# charger_v4.net
KiCad netlist of a schematic drawn in EAGLE
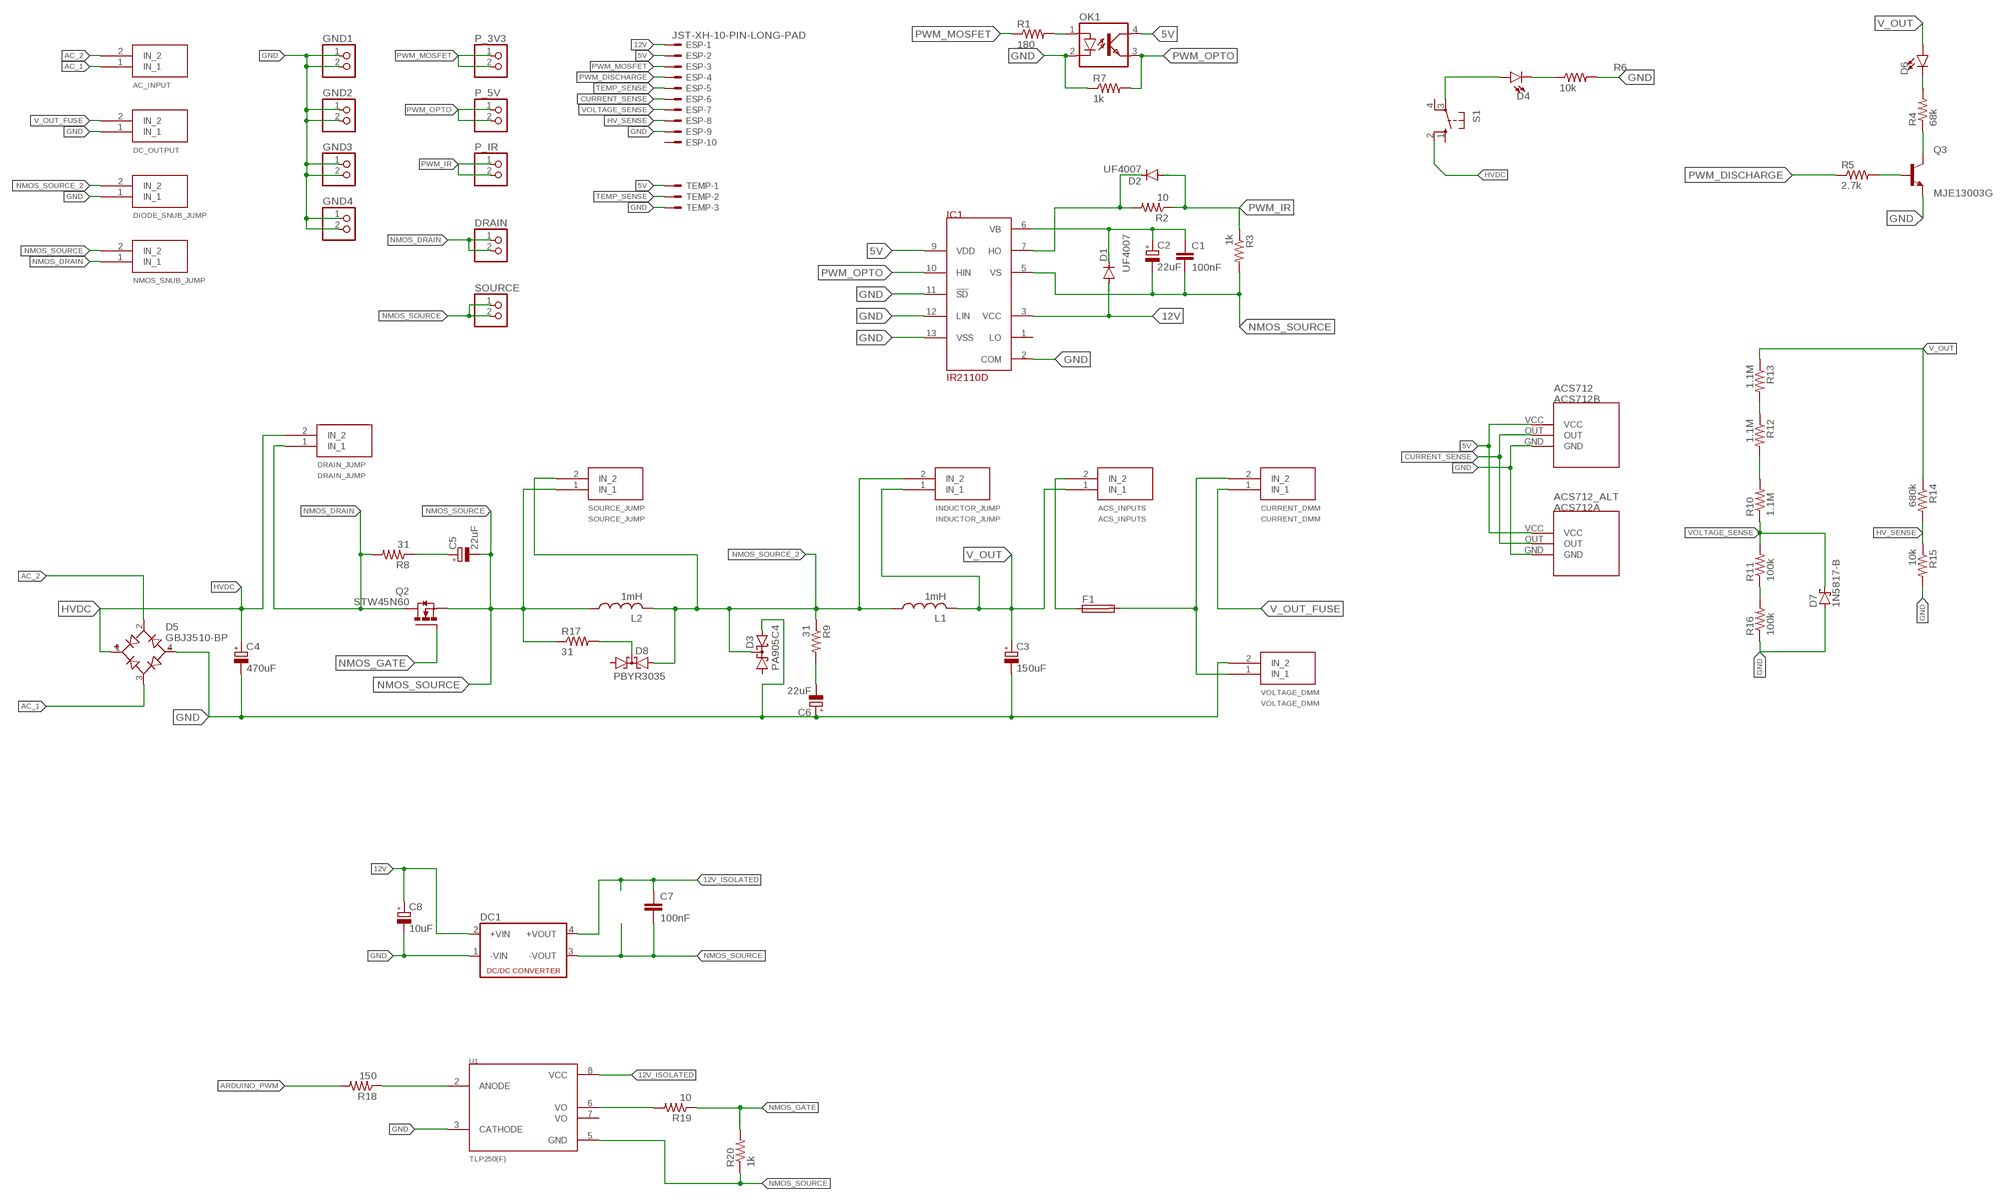
[diagram p0: schematic, sheet 1]

(export (version "E")
  (design (tool "Eeschema 10.0.6"))
  (components
    (comp (ref "ACS712")
      (value "ACS712B")
      (footprint "eagle-import:ACS712-2")
      (libsource (lib "eagle-import") (part "ACS712B"))
    )
    (comp (ref "ACS712_ALT")
      (value "ACS712A")
      (footprint "eagle-import:ACS712-1")
      (libsource (lib "eagle-import") (part "ACS712A"))
    )
    (comp (ref "ACS_INPUTS")
      (value "ACS_INPUTS")
      (footprint "eagle-import:TERMINAL_2P")
      (libsource (lib "eagle-import") (part "TERMINAL_2P"))
    )
    (comp (ref "AC_INPUT")
      (value "AC_INPUT")
      (footprint "eagle-import:TERMINAL_2P")
      (libsource (lib "eagle-import") (part "TERMINAL_2P"))
    )
    (comp (ref "C1")
      (value "100nF")
      (footprint "eagle-import:C025-025X050")
      (libsource (lib "eagle-import") (part "C-EU025-025X050"))
    )
    (comp (ref "C2")
      (value "22uF")
      (footprint "eagle-import:E2,5-6E")
      (libsource (lib "eagle-import") (part "CPOL-EUE2,5-6E"))
    )
    (comp (ref "C3")
      (value "150uF")
      (footprint "eagle-import:E7,5-18")
      (libsource (lib "eagle-import") (part "CPOL-EUE7.5-18"))
    )
    (comp (ref "C4")
      (value "470uF")
      (footprint "eagle-import:EB35D")
      (libsource (lib "eagle-import") (part "CPOL-EUE10-35"))
    )
    (comp (ref "C5")
      (value "22uF")
      (footprint "eagle-import:ETR4")
      (libsource (lib "eagle-import") (part "CPOL-EUETR4"))
    )
    (comp (ref "C6")
      (value "22uF")
      (footprint "eagle-import:ETR4")
      (libsource (lib "eagle-import") (part "CPOL-EUETR4"))
    )
    (comp (ref "C7")
      (value "100nF")
      (footprint "eagle-import:C025-025X050")
      (libsource (lib "eagle-import") (part "C-EU025-025X050"))
    )
    (comp (ref "C8")
      (value "10uF")
      (footprint "eagle-import:E2,5-6E")
      (libsource (lib "eagle-import") (part "CPOL-EUE2,5-6E"))
    )
    (comp (ref "CURRENT_DMM")
      (value "CURRENT_DMM")
      (footprint "eagle-import:TERMINAL_2P")
      (libsource (lib "eagle-import") (part "TERMINAL_2P"))
    )
    (comp (ref "D1")
      (value "UF4007")
      (footprint "eagle-import:DO34-7")
      (libsource (lib "eagle-import") (part "BAS15"))
    )
    (comp (ref "D2")
      (value "UF4007")
      (footprint "eagle-import:DO34-7")
      (libsource (lib "eagle-import") (part "BAS15"))
    )
    (comp (ref "D3")
      (value "PA905C4")
      (footprint "eagle-import:SOT93S")
      (libsource (lib "eagle-import") (part "PBYR3035"))
    )
    (comp (ref "D4")
      (value "LED5MM")
      (footprint "eagle-import:LED_5MM")
      (libsource (lib "eagle-import") (part "LED5MM"))
    )
    (comp (ref "D5")
      (value "GBJ3510-BP")
      (footprint "eagle-import:DIOB_GBJ3510-BP")
      (fields (field (name "MF") "Micro Commercial"))
      (libsource (lib "eagle-import") (part "GBJ3510-BP"))
    )
    (comp (ref "D6")
      (value "LED5MM")
      (footprint "eagle-import:LED_5MM")
      (libsource (lib "eagle-import") (part "LED5MM"))
    )
    (comp (ref "D7")
      (value "1N5817-B")
      (footprint "eagle-import:DO41-7.6")
      (libsource (lib "eagle-import") (part "1N5817-B"))
    )
    (comp (ref "D8")
      (value "PBYR3035")
      (footprint "eagle-import:SOT93S")
      (libsource (lib "eagle-import") (part "PBYR3035"))
    )
    (comp (ref "DC1")
      (value "NME")
      (footprint "eagle-import:NME")
      (fields (field (name "MF") "C & D TECHNOLOGIES, INC") (field (name "MPN") "NME1205D"))
      (libsource (lib "eagle-import") (part "NME"))
    )
    (comp (ref "DC_OUTPUT")
      (value "DC_OUTPUT")
      (footprint "eagle-import:TERMINAL_2P")
      (libsource (lib "eagle-import") (part "TERMINAL_2P"))
    )
    (comp (ref "DIODE_SNUB_JUMP")
      (value "DIODE_SNUB_JUMP")
      (footprint "eagle-import:TERMINAL_2P")
      (libsource (lib "eagle-import") (part "TERMINAL_2P"))
    )
    (comp (ref "DRAIN")
      (value "PINHD-1X2")
      (footprint "eagle-import:1X02")
      (libsource (lib "eagle-import") (part "PINHD-1X2"))
    )
    (comp (ref "DRAIN_JUMP")
      (value "DRAIN_JUMP")
      (footprint "eagle-import:TERMINAL_2P")
      (libsource (lib "eagle-import") (part "TERMINAL_2P"))
    )
    (comp (ref "ESP")
      (value "JST-XH-10-PIN-LONG-PAD")
      (footprint "eagle-import:JST-XH-10-PACKAGE-LONG-PAD")
      (libsource (lib "eagle-import") (part "JST-XH-10-PIN-LONG-PAD"))
    )
    (comp (ref "F1")
      (value "FUSEHOLDER")
      (footprint "eagle-import:FUSEHOLDER")
      (fields (field (name "MPN") "0031.7701.11"))
      (libsource (lib "eagle-import") (part "FUSEHOLDER"))
    )
    (comp (ref "GND1")
      (value "PINHD-1X2")
      (footprint "eagle-import:1X02")
      (libsource (lib "eagle-import") (part "PINHD-1X2"))
    )
    (comp (ref "GND2")
      (value "PINHD-1X2")
      (footprint "eagle-import:1X02")
      (libsource (lib "eagle-import") (part "PINHD-1X2"))
    )
    (comp (ref "GND3")
      (value "PINHD-1X2")
      (footprint "eagle-import:1X02")
      (libsource (lib "eagle-import") (part "PINHD-1X2"))
    )
    (comp (ref "GND4")
      (value "PINHD-1X2")
      (footprint "eagle-import:1X02")
      (libsource (lib "eagle-import") (part "PINHD-1X2"))
    )
    (comp (ref "IC1")
      (value "IR2110D")
      (footprint "eagle-import:DIL14")
      (libsource (lib "eagle-import") (part "IR2110D"))
    )
    (comp (ref "INDUCTOR_JUMP")
      (value "INDUCTOR_JUMP")
      (footprint "eagle-import:TERMINAL_2P")
      (libsource (lib "eagle-import") (part "TERMINAL_2P"))
    )
    (comp (ref "L1")
      (value "1mH")
      (footprint "eagle-import:TJ7-U1")
      (libsource (lib "eagle-import") (part "L-USTJ7-U1"))
    )
    (comp (ref "L2")
      (value "1mH")
      (footprint "eagle-import:TJ7-U1")
      (libsource (lib "eagle-import") (part "L-USTJ7-U1"))
    )
    (comp (ref "NMOS_SNUB_JUMP")
      (value "NMOS_SNUB_JUMP")
      (footprint "eagle-import:TERMINAL_2P")
      (libsource (lib "eagle-import") (part "TERMINAL_2P"))
    )
    (comp (ref "OK1")
      (value "SFH618A-5")
      (footprint "eagle-import:DIP4")
      (fields (field (name "MF") "VISHAY/TELEFUNKEN"))
      (libsource (lib "eagle-import") (part "SFH618?A-5"))
    )
    (comp (ref "P_3V3")
      (value "PINHD-1X2")
      (footprint "eagle-import:1X02")
      (libsource (lib "eagle-import") (part "PINHD-1X2"))
    )
    (comp (ref "P_5V")
      (value "PINHD-1X2")
      (footprint "eagle-import:1X02")
      (libsource (lib "eagle-import") (part "PINHD-1X2"))
    )
    (comp (ref "P_IR")
      (value "PINHD-1X2")
      (footprint "eagle-import:1X02")
      (libsource (lib "eagle-import") (part "PINHD-1X2"))
    )
    (comp (ref "Q2")
      (value "STW45N60")
      (footprint "eagle-import:TO247AC")
      (fields (field (name "MF") "Vishay Siliconix") (field (name "MP") "IRFP240"))
      (libsource (lib "eagle-import") (part "IRFP240"))
    )
    (comp (ref "Q3")
      (value "MJE13003G")
      (footprint "eagle-import:TO229P780X300X1364-3")
      (fields (field (name "MF") "ON Semiconductor"))
      (libsource (lib "eagle-import") (part "MJE13003G"))
    )
    (comp (ref "R1")
      (value "180")
      (footprint "eagle-import:0204_7")
      (libsource (lib "eagle-import") (part "R-US_0204/7"))
    )
    (comp (ref "R2")
      (value "10")
      (footprint "eagle-import:0204_7")
      (libsource (lib "eagle-import") (part "R-US_0204/7"))
    )
    (comp (ref "R3")
      (value "1k")
      (footprint "eagle-import:0204_7")
      (libsource (lib "eagle-import") (part "R-US_0204/7"))
    )
    (comp (ref "R4")
      (value "68k")
      (footprint "eagle-import:0411_15")
      (libsource (lib "eagle-import") (part "R-US_0411/15"))
    )
    (comp (ref "R5")
      (value "2.7k")
      (footprint "eagle-import:0204_7")
      (libsource (lib "eagle-import") (part "R-US_0204/7"))
    )
    (comp (ref "R6")
      (value "10k")
      (footprint "eagle-import:0204_7")
      (libsource (lib "eagle-import") (part "R-US_0204/7"))
    )
    (comp (ref "R7")
      (value "1k")
      (footprint "eagle-import:0204_7")
      (libsource (lib "eagle-import") (part "R-US_0204/7"))
    )
    (comp (ref "R8")
      (value "31")
      (footprint "eagle-import:0411_15")
      (libsource (lib "eagle-import") (part "R-US_0411/15"))
    )
    (comp (ref "R9")
      (value "31")
      (footprint "eagle-import:0411_15")
      (libsource (lib "eagle-import") (part "R-US_0411/15"))
    )
    (comp (ref "R10")
      (value "1.1M")
      (footprint "eagle-import:R0805")
      (libsource (lib "eagle-import") (part "R-US_R0805"))
    )
    (comp (ref "R11")
      (value "100k")
      (footprint "eagle-import:R0805")
      (libsource (lib "eagle-import") (part "R-US_R0805"))
    )
    (comp (ref "R12")
      (value "1.1M")
      (footprint "eagle-import:R0805")
      (libsource (lib "eagle-import") (part "R-US_R0805"))
    )
    (comp (ref "R13")
      (value "1.1M")
      (footprint "eagle-import:R0805")
      (libsource (lib "eagle-import") (part "R-US_R0805"))
    )
    (comp (ref "R14")
      (value "680k")
      (footprint "eagle-import:0207_10")
      (libsource (lib "eagle-import") (part "R-US_0207/10"))
    )
    (comp (ref "R15")
      (value "10k")
      (footprint "eagle-import:0207_10")
      (libsource (lib "eagle-import") (part "R-US_0207/10"))
    )
    (comp (ref "R16")
      (value "100k")
      (footprint "eagle-import:R0805")
      (libsource (lib "eagle-import") (part "R-US_R0805"))
    )
    (comp (ref "R17")
      (value "31")
      (footprint "eagle-import:0411_15")
      (libsource (lib "eagle-import") (part "R-US_0411/15"))
    )
    (comp (ref "R18")
      (value "150")
      (footprint "eagle-import:0204_7")
      (libsource (lib "eagle-import") (part "R-US_0204/7"))
    )
    (comp (ref "R19")
      (value "10")
      (footprint "eagle-import:0204_7")
      (libsource (lib "eagle-import") (part "R-US_0204/7"))
    )
    (comp (ref "R20")
      (value "1k")
      (footprint "eagle-import:0204_7")
      (libsource (lib "eagle-import") (part "R-US_0204/7"))
    )
    (comp (ref "S1")
      (value "10-XX")
      (footprint "eagle-import:B3F-10XX")
      (fields (field (name "MPN") "B3F-1000"))
      (libsource (lib "eagle-import") (part "10-XX"))
    )
    (comp (ref "SOURCE")
      (value "PINHD-1X2")
      (footprint "eagle-import:1X02")
      (libsource (lib "eagle-import") (part "PINHD-1X2"))
    )
    (comp (ref "SOURCE_JUMP")
      (value "SOURCE_JUMP")
      (footprint "eagle-import:TERMINAL_2P")
      (libsource (lib "eagle-import") (part "TERMINAL_2P"))
    )
    (comp (ref "TEMP")
      (value "JST-XH-03-PIN-LONG-PAD")
      (footprint "eagle-import:JST-XH-03-PACKAGE-LONG-PAD")
      (libsource (lib "eagle-import") (part "JST-XH-03-PIN-LONG-PAD"))
    )
    (comp (ref "U1")
      (value "TLP250(F)")
      (footprint "eagle-import:DIP1016W50P254L966H380Q8P")
      (fields (field (name "MF") "Toshiba"))
      (libsource (lib "eagle-import") (part "TLP250(F)"))
    )
    (comp (ref "VOLTAGE_DMM")
      (value "VOLTAGE_DMM")
      (footprint "eagle-import:TERMINAL_2P")
      (libsource (lib "eagle-import") (part "TERMINAL_2P"))
    )
  )
  (nets
    (net (code "1") (name "5V") (class "Default")
      (node (ref "ACS712") (pin "VCC") (pinfunction "VCC_VCC") (pintype "bidirectional"))
      (node (ref "ACS712_ALT") (pin "VCC") (pinfunction "VCC_VCC") (pintype "bidirectional"))
      (node (ref "ESP") (pin "2") (pinfunction "S_2") (pintype "passive"))
      (node (ref "IC1") (pin "9") (pinfunction "VDD_9") (pintype "power_in"))
      (node (ref "OK1") (pin "4") (pinfunction "COL_4") (pintype "passive"))
      (node (ref "TEMP") (pin "1") (pinfunction "S_1") (pintype "passive"))
    )
    (net (code "2") (name "12V") (class "Default")
      (node (ref "C8") (pin "+") (pinfunction "+_+") (pintype "passive"))
      (node (ref "D1") (pin "A") (pinfunction "A_A") (pintype "passive"))
      (node (ref "DC1") (pin "2") (pinfunction "+VIN_2") (pintype "passive"))
      (node (ref "ESP") (pin "1") (pinfunction "S_1") (pintype "passive"))
      (node (ref "IC1") (pin "3") (pinfunction "VCC_3") (pintype "power_in"))
    )
    (net (code "3") (name "12V_ISOLATED") (class "Default")
      (node (ref "C7") (pin "1") (pinfunction "1_1") (pintype "passive"))
      (node (ref "DC1") (pin "4") (pinfunction "+VOUT_4") (pintype "passive"))
      (node (ref "U1") (pin "8") (pinfunction "VCC_8") (pintype "power_in"))
    )
    (net (code "4") (name "AC_1") (class "Default")
      (node (ref "AC_INPUT") (pin "1") (pinfunction "IN_1_1") (pintype "bidirectional"))
      (node (ref "D5") (pin "3") (pinfunction "AC2_3") (pintype "passive"))
    )
    (net (code "5") (name "AC_2") (class "Default")
      (node (ref "AC_INPUT") (pin "2") (pinfunction "IN_2_2") (pintype "bidirectional"))
      (node (ref "D5") (pin "2") (pinfunction "AC1_2") (pintype "passive"))
    )
    (net (code "6") (name "ARDUINO_PWM") (class "Default")
      (node (ref "R18") (pin "2") (pinfunction "2_2") (pintype "passive"))
    )
    (net (code "7") (name "CURRENT_SENSE") (class "Default")
      (node (ref "ACS712") (pin "OUT") (pinfunction "OUT_OUT") (pintype "bidirectional"))
      (node (ref "ACS712_ALT") (pin "OUT") (pinfunction "OUT_OUT") (pintype "bidirectional"))
      (node (ref "ESP") (pin "6") (pinfunction "S_6") (pintype "passive"))
    )
    (net (code "8") (name "GND") (class "Default")
      (node (ref "ACS712") (pin "GND") (pinfunction "GND_GND") (pintype "bidirectional"))
      (node (ref "ACS712_ALT") (pin "GND") (pinfunction "GND_GND") (pintype "bidirectional"))
      (node (ref "C3") (pin "-") (pinfunction "-_-") (pintype "passive"))
      (node (ref "C4") (pin "-") (pinfunction "-_-") (pintype "passive"))
      (node (ref "C6") (pin "+") (pinfunction "+_+") (pintype "passive"))
      (node (ref "C8") (pin "-") (pinfunction "-_-") (pintype "passive"))
      (node (ref "D3") (pin "A2") (pinfunction "A2_A2") (pintype "passive"))
      (node (ref "D5") (pin "4") (pinfunction "-_4") (pintype "passive"))
      (node (ref "D7") (pin "A") (pinfunction "A_A") (pintype "passive"))
      (node (ref "DC1") (pin "1") (pinfunction "-VIN_1") (pintype "passive"))
      (node (ref "DC_OUTPUT") (pin "1") (pinfunction "IN_1_1") (pintype "bidirectional"))
      (node (ref "DIODE_SNUB_JUMP") (pin "1") (pinfunction "IN_1_1") (pintype "bidirectional"))
      (node (ref "ESP") (pin "9") (pinfunction "S_9") (pintype "passive"))
      (node (ref "GND1") (pin "1") (pinfunction "1_1") (pintype "passive"))
      (node (ref "GND1") (pin "2") (pinfunction "2_2") (pintype "passive"))
      (node (ref "GND2") (pin "1") (pinfunction "1_1") (pintype "passive"))
      (node (ref "GND2") (pin "2") (pinfunction "2_2") (pintype "passive"))
      (node (ref "GND3") (pin "1") (pinfunction "1_1") (pintype "passive"))
      (node (ref "GND3") (pin "2") (pinfunction "2_2") (pintype "passive"))
      (node (ref "GND4") (pin "1") (pinfunction "1_1") (pintype "passive"))
      (node (ref "GND4") (pin "2") (pinfunction "2_2") (pintype "passive"))
      (node (ref "IC1") (pin "11") (pinfunction "~{SD}_11") (pintype "input"))
      (node (ref "IC1") (pin "12") (pinfunction "LIN_12") (pintype "input"))
      (node (ref "IC1") (pin "13") (pinfunction "VSS_13") (pintype "power_in"))
      (node (ref "IC1") (pin "2") (pinfunction "COM_2") (pintype "power_in"))
      (node (ref "OK1") (pin "2") (pinfunction "C_2") (pintype "passive"))
      (node (ref "Q3") (pin "3") (pinfunction "E_3") (pintype "passive"))
      (node (ref "R15") (pin "2") (pinfunction "2_2") (pintype "passive"))
      (node (ref "R16") (pin "1") (pinfunction "1_1") (pintype "passive"))
      (node (ref "R6") (pin "2") (pinfunction "2_2") (pintype "passive"))
      (node (ref "R7") (pin "1") (pinfunction "1_1") (pintype "passive"))
      (node (ref "TEMP") (pin "3") (pinfunction "S_3") (pintype "passive"))
      (node (ref "U1") (pin "3") (pinfunction "CATHODE_3") (pintype "passive"))
      (node (ref "VOLTAGE_DMM") (pin "2") (pinfunction "IN_2_2") (pintype "bidirectional"))
    )
    (net (code "9") (name "HVDC") (class "Default")
      (node (ref "C4") (pin "+") (pinfunction "+_+") (pintype "passive"))
      (node (ref "D5") (pin "1") (pinfunction "+_1") (pintype "passive"))
      (node (ref "DRAIN_JUMP") (pin "2") (pinfunction "IN_2_2") (pintype "bidirectional"))
      (node (ref "S1") (pin "2") (pinfunction "S1_2") (pintype "passive"))
    )
    (net (code "10") (name "HV_SENSE") (class "Default")
      (node (ref "ESP") (pin "8") (pinfunction "S_8") (pintype "passive"))
      (node (ref "R14") (pin "2") (pinfunction "2_2") (pintype "passive"))
      (node (ref "R15") (pin "1") (pinfunction "1_1") (pintype "passive"))
    )
    (net (code "11") (name "NMOS_DRAIN") (class "Default")
      (node (ref "DRAIN") (pin "1") (pinfunction "1_1") (pintype "passive"))
      (node (ref "DRAIN") (pin "2") (pinfunction "2_2") (pintype "passive"))
      (node (ref "DRAIN_JUMP") (pin "1") (pinfunction "IN_1_1") (pintype "bidirectional"))
      (node (ref "NMOS_SNUB_JUMP") (pin "1") (pinfunction "IN_1_1") (pintype "bidirectional"))
      (node (ref "Q2") (pin "2") (pinfunction "D_2") (pintype "passive"))
      (node (ref "R8") (pin "2") (pinfunction "2_2") (pintype "passive"))
    )
    (net (code "12") (name "NMOS_GATE") (class "Default")
      (node (ref "Q2") (pin "1") (pinfunction "G_1") (pintype "passive"))
      (node (ref "R19") (pin "1") (pinfunction "1_1") (pintype "passive"))
      (node (ref "R20") (pin "2") (pinfunction "2_2") (pintype "passive"))
    )
    (net (code "13") (name "NMOS_SOURCE") (class "Default")
      (node (ref "C1") (pin "2") (pinfunction "2_2") (pintype "passive"))
      (node (ref "C2") (pin "-") (pinfunction "-_-") (pintype "passive"))
      (node (ref "C5") (pin "-") (pinfunction "-_-") (pintype "passive"))
      (node (ref "C7") (pin "2") (pinfunction "2_2") (pintype "passive"))
      (node (ref "DC1") (pin "3") (pinfunction "-VOUT_3") (pintype "passive"))
      (node (ref "IC1") (pin "5") (pinfunction "VS_5") (pintype "power_in"))
      (node (ref "L2") (pin "1") (pinfunction "1_1") (pintype "passive"))
      (node (ref "NMOS_SNUB_JUMP") (pin "2") (pinfunction "IN_2_2") (pintype "bidirectional"))
      (node (ref "Q2") (pin "3") (pinfunction "S_3") (pintype "passive"))
      (node (ref "R17") (pin "1") (pinfunction "1_1") (pintype "passive"))
      (node (ref "R20") (pin "1") (pinfunction "1_1") (pintype "passive"))
      (node (ref "R3") (pin "2") (pinfunction "2_2") (pintype "passive"))
      (node (ref "SOURCE") (pin "1") (pinfunction "1_1") (pintype "passive"))
      (node (ref "SOURCE") (pin "2") (pinfunction "2_2") (pintype "passive"))
      (node (ref "SOURCE_JUMP") (pin "1") (pinfunction "IN_1_1") (pintype "bidirectional"))
      (node (ref "U1") (pin "5") (pinfunction "GND_5") (pintype "power_in"))
    )
    (net (code "14") (name "NMOS_SOURCE_2") (class "Default")
      (node (ref "D3") (pin "C") (pinfunction "C_C") (pintype "passive"))
      (node (ref "D8") (pin "A2") (pinfunction "A2_A2") (pintype "passive"))
      (node (ref "DIODE_SNUB_JUMP") (pin "2") (pinfunction "IN_2_2") (pintype "bidirectional"))
      (node (ref "INDUCTOR_JUMP") (pin "2") (pinfunction "IN_2_2") (pintype "bidirectional"))
      (node (ref "L1") (pin "1") (pinfunction "1_1") (pintype "passive"))
      (node (ref "L2") (pin "2") (pinfunction "2_2") (pintype "passive"))
      (node (ref "R9") (pin "1") (pinfunction "1_1") (pintype "passive"))
      (node (ref "SOURCE_JUMP") (pin "2") (pinfunction "IN_2_2") (pintype "bidirectional"))
    )
    (net (code "15") (name "Net-(ACS_INPUTS-IN_2)") (class "Default")
      (node (ref "ACS_INPUTS") (pin "2") (pinfunction "IN_2_2") (pintype "bidirectional"))
      (node (ref "F1") (pin "1") (pinfunction "1_1") (pintype "passive"))
    )
    (net (code "16") (name "Net-(C5-Pad+)") (class "Default")
      (node (ref "C5") (pin "+") (pinfunction "+_+") (pintype "passive"))
      (node (ref "R8") (pin "1") (pinfunction "1_1") (pintype "passive"))
    )
    (net (code "17") (name "Net-(C6-Pad-)") (class "Default")
      (node (ref "C6") (pin "-") (pinfunction "-_-") (pintype "passive"))
      (node (ref "R9") (pin "2") (pinfunction "2_2") (pintype "passive"))
    )
    (net (code "18") (name "Net-(CURRENT_DMM-IN_2)") (class "Default")
      (node (ref "CURRENT_DMM") (pin "2") (pinfunction "IN_2_2") (pintype "bidirectional"))
      (node (ref "F1") (pin "2") (pinfunction "2_2") (pintype "passive"))
      (node (ref "VOLTAGE_DMM") (pin "1") (pinfunction "IN_1_1") (pintype "bidirectional"))
    )
    (net (code "19") (name "Net-(D4-C)") (class "Default")
      (node (ref "D4") (pin "K") (pinfunction "C_K") (pintype "passive"))
      (node (ref "R6") (pin "1") (pinfunction "1_1") (pintype "passive"))
    )
    (net (code "20") (name "Net-(D6-C)") (class "Default")
      (node (ref "D6") (pin "K") (pinfunction "C_K") (pintype "passive"))
      (node (ref "R4") (pin "2") (pinfunction "2_2") (pintype "passive"))
    )
    (net (code "21") (name "Net-(D8-PadC)") (class "Default")
      (node (ref "D8") (pin "C") (pinfunction "C_C") (pintype "passive"))
      (node (ref "R17") (pin "2") (pinfunction "2_2") (pintype "passive"))
    )
    (net (code "22") (name "Net-(IC1-HO)") (class "Default")
      (node (ref "D2") (pin "C") (pinfunction "C_C") (pintype "passive"))
      (node (ref "IC1") (pin "7") (pinfunction "HO_7") (pintype "output"))
      (node (ref "R2") (pin "2") (pinfunction "2_2") (pintype "passive"))
    )
    (net (code "23") (name "Net-(IC1-VB)") (class "Default")
      (node (ref "C1") (pin "1") (pinfunction "1_1") (pintype "passive"))
      (node (ref "C2") (pin "+") (pinfunction "+_+") (pintype "passive"))
      (node (ref "D1") (pin "C") (pinfunction "C_C") (pintype "passive"))
      (node (ref "IC1") (pin "6") (pinfunction "VB_6") (pintype "power_in"))
    )
    (net (code "24") (name "Net-(OK1-A)") (class "Default")
      (node (ref "OK1") (pin "1") (pinfunction "A_1") (pintype "passive"))
      (node (ref "R1") (pin "2") (pinfunction "2_2") (pintype "passive"))
    )
    (net (code "25") (name "Net-(Q3-B)") (class "Default")
      (node (ref "Q3") (pin "1") (pinfunction "B_1") (pintype "passive"))
      (node (ref "R5") (pin "2") (pinfunction "2_2") (pintype "passive"))
    )
    (net (code "26") (name "Net-(Q3-C)") (class "Default")
      (node (ref "Q3") (pin "2") (pinfunction "C_2") (pintype "passive"))
      (node (ref "R4") (pin "1") (pinfunction "1_1") (pintype "passive"))
    )
    (net (code "27") (name "Net-(R10-Pad2)") (class "Default")
      (node (ref "R10") (pin "2") (pinfunction "2_2") (pintype "passive"))
      (node (ref "R12") (pin "2") (pinfunction "2_2") (pintype "passive"))
    )
    (net (code "28") (name "Net-(R11-Pad1)") (class "Default")
      (node (ref "R11") (pin "1") (pinfunction "1_1") (pintype "passive"))
      (node (ref "R16") (pin "2") (pinfunction "2_2") (pintype "passive"))
    )
    (net (code "29") (name "Net-(R12-Pad1)") (class "Default")
      (node (ref "R12") (pin "1") (pinfunction "1_1") (pintype "passive"))
      (node (ref "R13") (pin "2") (pinfunction "2_2") (pintype "passive"))
    )
    (net (code "30") (name "Net-(R19-Pad2)") (class "Default")
      (node (ref "R19") (pin "2") (pinfunction "2_2") (pintype "passive"))
      (node (ref "U1") (pin "6") (pinfunction "VO_6") (pintype "output"))
    )
    (net (code "31") (name "Net-(S1-P)") (class "Default")
      (node (ref "D4") (pin "A") (pinfunction "A_A") (pintype "passive"))
      (node (ref "S1") (pin "3") (pinfunction "P_3") (pintype "passive"))
    )
    (net (code "32") (name "Net-(U1-ANODE)") (class "Default")
      (node (ref "R18") (pin "1") (pinfunction "1_1") (pintype "passive"))
      (node (ref "U1") (pin "2") (pinfunction "ANODE_2") (pintype "passive"))
    )
    (net (code "33") (name "PWM_DISCHARGE") (class "Default")
      (node (ref "ESP") (pin "4") (pinfunction "S_4") (pintype "passive"))
      (node (ref "R5") (pin "1") (pinfunction "1_1") (pintype "passive"))
    )
    (net (code "34") (name "PWM_IR") (class "Default")
      (node (ref "D2") (pin "A") (pinfunction "A_A") (pintype "passive"))
      (node (ref "P_IR") (pin "1") (pinfunction "1_1") (pintype "passive"))
      (node (ref "P_IR") (pin "2") (pinfunction "2_2") (pintype "passive"))
      (node (ref "R2") (pin "1") (pinfunction "1_1") (pintype "passive"))
      (node (ref "R3") (pin "1") (pinfunction "1_1") (pintype "passive"))
    )
    (net (code "35") (name "PWM_MOSFET") (class "Default")
      (node (ref "ESP") (pin "3") (pinfunction "S_3") (pintype "passive"))
      (node (ref "P_3V3") (pin "1") (pinfunction "1_1") (pintype "passive"))
      (node (ref "P_3V3") (pin "2") (pinfunction "2_2") (pintype "passive"))
      (node (ref "R1") (pin "1") (pinfunction "1_1") (pintype "passive"))
    )
    (net (code "36") (name "PWM_OPTO") (class "Default")
      (node (ref "IC1") (pin "10") (pinfunction "HIN_10") (pintype "input"))
      (node (ref "OK1") (pin "3") (pinfunction "EMIT_3") (pintype "passive"))
      (node (ref "P_5V") (pin "1") (pinfunction "1_1") (pintype "passive"))
      (node (ref "P_5V") (pin "2") (pinfunction "2_2") (pintype "passive"))
      (node (ref "R7") (pin "2") (pinfunction "2_2") (pintype "passive"))
    )
    (net (code "37") (name "TEMP_SENSE") (class "Default")
      (node (ref "ESP") (pin "5") (pinfunction "S_5") (pintype "passive"))
      (node (ref "TEMP") (pin "2") (pinfunction "S_2") (pintype "passive"))
    )
    (net (code "38") (name "VOLTAGE_SENSE") (class "Default")
      (node (ref "D7") (pin "C") (pinfunction "C_C") (pintype "passive"))
      (node (ref "ESP") (pin "7") (pinfunction "S_7") (pintype "passive"))
      (node (ref "R10") (pin "1") (pinfunction "1_1") (pintype "passive"))
      (node (ref "R11") (pin "2") (pinfunction "2_2") (pintype "passive"))
    )
    (net (code "39") (name "V_OUT") (class "Default")
      (node (ref "ACS_INPUTS") (pin "1") (pinfunction "IN_1_1") (pintype "bidirectional"))
      (node (ref "C3") (pin "+") (pinfunction "+_+") (pintype "passive"))
      (node (ref "D6") (pin "A") (pinfunction "A_A") (pintype "passive"))
      (node (ref "INDUCTOR_JUMP") (pin "1") (pinfunction "IN_1_1") (pintype "bidirectional"))
      (node (ref "L1") (pin "2") (pinfunction "2_2") (pintype "passive"))
      (node (ref "R13") (pin "1") (pinfunction "1_1") (pintype "passive"))
      (node (ref "R14") (pin "1") (pinfunction "1_1") (pintype "passive"))
    )
    (net (code "40") (name "V_OUT_FUSE") (class "Default")
      (node (ref "CURRENT_DMM") (pin "1") (pinfunction "IN_1_1") (pintype "bidirectional"))
      (node (ref "DC_OUTPUT") (pin "2") (pinfunction "IN_2_2") (pintype "bidirectional"))
    )
    (net (code "41") (name "unconnected-(D3-PadA1)") (class "Default")
      (node (ref "D3") (pin "A1") (pinfunction "A1_A1") (pintype "passive"))
    )
    (net (code "42") (name "unconnected-(D8-PadA1)") (class "Default")
      (node (ref "D8") (pin "A1") (pinfunction "A1_A1") (pintype "passive"))
    )
    (net (code "43") (name "unconnected-(ESPB-S-Pad10)") (class "Default")
      (node (ref "ESP") (pin "10") (pinfunction "S_10") (pintype "passive"))
    )
    (net (code "44") (name "unconnected-(IC1-LO-Pad1)") (class "Default")
      (node (ref "IC1") (pin "1") (pinfunction "LO_1") (pintype "output"))
    )
    (net (code "45") (name "unconnected-(S1-P1-Pad4)") (class "Default")
      (node (ref "S1") (pin "4") (pinfunction "P1_4") (pintype "passive"))
    )
    (net (code "46") (name "unconnected-(S1-S-Pad1)") (class "Default")
      (node (ref "S1") (pin "1") (pinfunction "S_1") (pintype "passive"))
    )
    (net (code "47") (name "unconnected-(U1-VO-Pad7)") (class "Default")
      (node (ref "U1") (pin "7") (pinfunction "VO_7") (pintype "output"))
    )
  )
)
